# LM704A0_5V0_PINOUT.net
KiCad netlist of a schematic drawn in Altium Designer
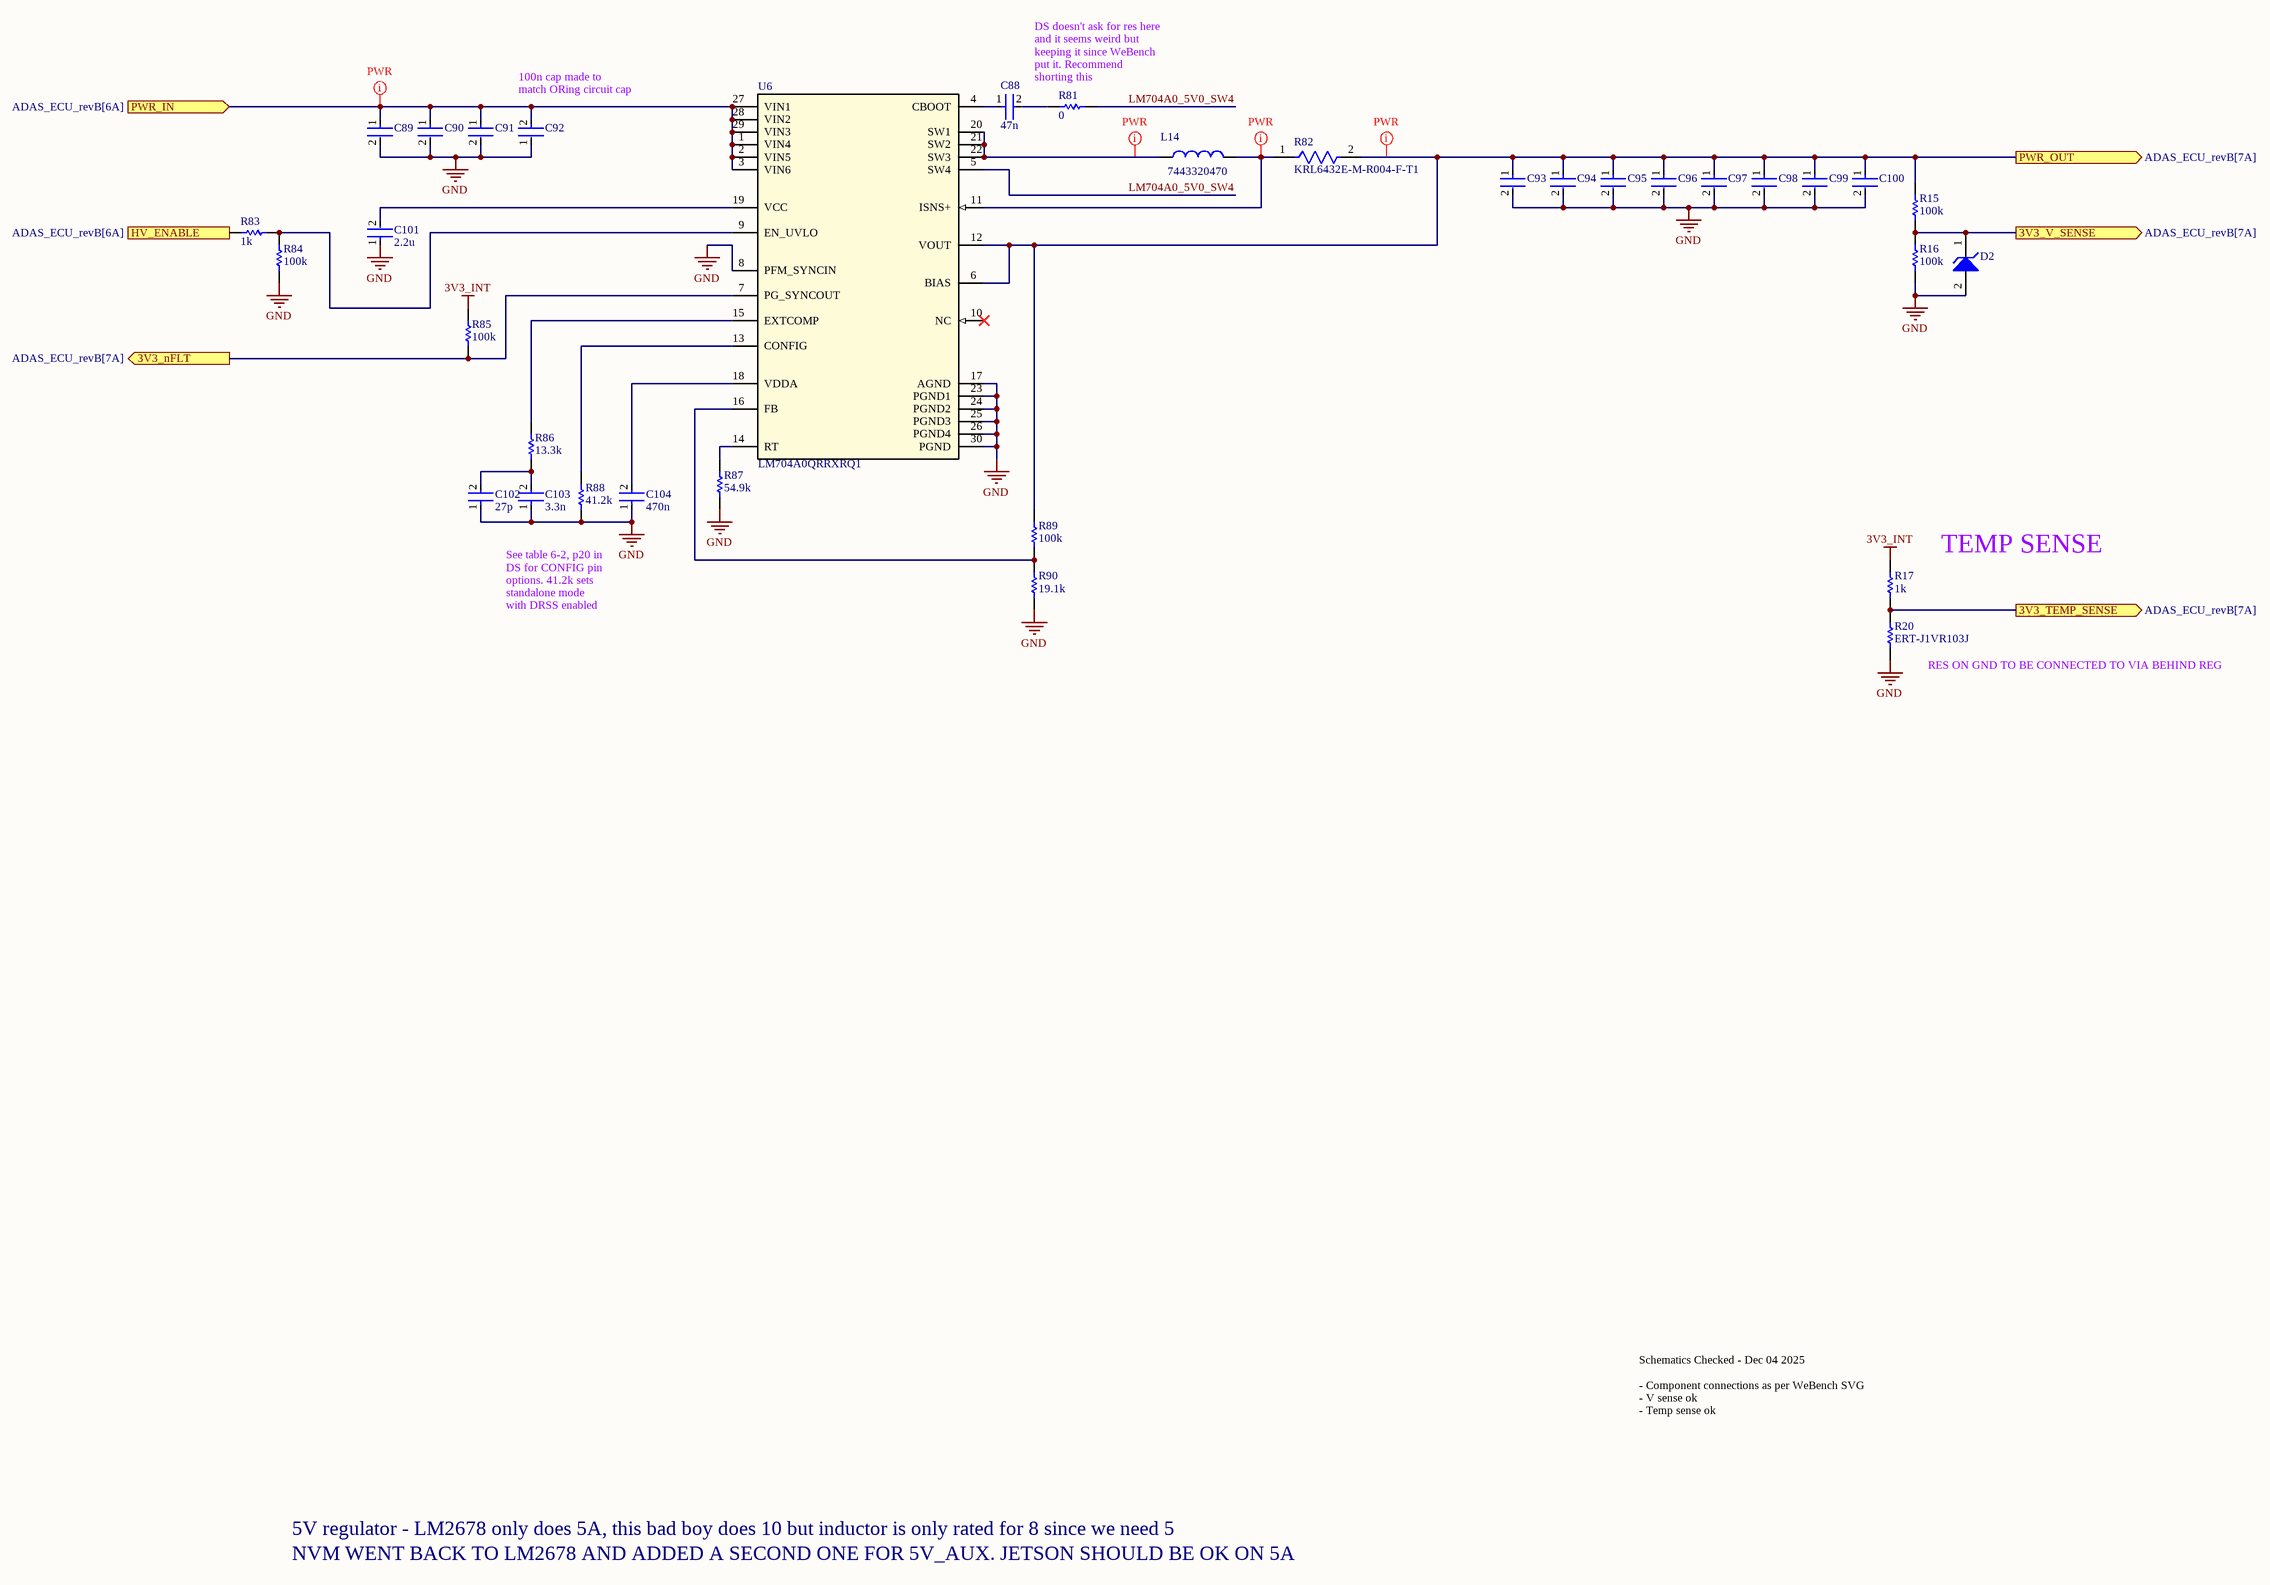
[diagram p0: LM704A0_5V0_PINOUT.SchDoc]

(export (version "E")
  (design (tool "Eeschema 10.0.6"))
  (components
    (comp (ref "C88")
      (value "47n")
      (footprint "FP-0402-L_1_0_0_05-W_0_5-IPC_A")
      (description "LARGE PADS, 0402 CAP, CHANGE COMMENT TO MATCH REAL P/N")
      (libsource (lib "Space Concordia") (part "b4654b650e69147ec39a6b967a45e02"))
    )
    (comp (ref "C89")
      (value "C3225X7R1H106M250AC")
      (footprint "FP-C3225-250-0_4-MFG")
      (description "Multilayer Ceramic Capacitors 10uF ±20% 50V X7R SMD 1210")
      (fields (field (name "TOLERANCE") "20%"))
      (libsource (lib "Altium Content Vault") (part "02cd4be3c70576c341d710602a673aa"))
    )
    (comp (ref "C90")
      (value "C3225X7R1H106M250AC")
      (footprint "FP-C3225-250-0_4-MFG")
      (description "Multilayer Ceramic Capacitors 10uF ±20% 50V X7R SMD 1210")
      (fields (field (name "TOLERANCE") "20%"))
      (libsource (lib "Altium Content Vault") (part "02cd4be3c70576c341d710602a673aa"))
    )
    (comp (ref "C91")
      (value "C3225X7R1H106M250AC")
      (footprint "FP-C3225-250-0_4-MFG")
      (description "Multilayer Ceramic Capacitors 10uF ±20% 50V X7R SMD 1210")
      (fields (field (name "TOLERANCE") "20%"))
      (libsource (lib "Altium Content Vault") (part "02cd4be3c70576c341d710602a673aa"))
    )
    (comp (ref "C92")
      (value "AC1210KKX7R0BB104")
      (footprint "FP-AC1210-0_85-MFG")
      (description "CAP CER 0.1UF 100V X7R 1210")
      (fields (field (name "MANUFACTURER") "Yageo") (field (name "TOLERANCE") "0.1"))
      (libsource (lib "Altium Content Vault") (part "236180d848d6139a670b325ea6854c9"))
    )
    (comp (ref "C93")
      (value "GRM32ER61C476KE15L")
      (footprint "FP-GRM32E-0_3-0_2-IPC_C")
      (description "CAP CER 47UF 16V X5R 1210")
      (fields (field (name "VOLTAGE") "16V") (field (name "TOLERANCE") "10%"))
      (libsource (lib "Altium Content Vault") (part "b4654b650e69147ec39a6b967a45e02"))
    )
    (comp (ref "C94")
      (value "GRM32ER61C476KE15L")
      (footprint "FP-GRM32E-0_3-0_2-IPC_C")
      (description "CAP CER 47UF 16V X5R 1210")
      (fields (field (name "VOLTAGE") "16V") (field (name "TOLERANCE") "10%"))
      (libsource (lib "Altium Content Vault") (part "b4654b650e69147ec39a6b967a45e02"))
    )
    (comp (ref "C95")
      (value "GRM32ER61C476KE15L")
      (footprint "FP-GRM32E-0_3-0_2-IPC_C")
      (description "CAP CER 47UF 16V X5R 1210")
      (fields (field (name "VOLTAGE") "16V") (field (name "TOLERANCE") "10%"))
      (libsource (lib "Altium Content Vault") (part "b4654b650e69147ec39a6b967a45e02"))
    )
    (comp (ref "C96")
      (value "GRM32ER61C476KE15L")
      (footprint "FP-GRM32E-0_3-0_2-IPC_C")
      (description "CAP CER 47UF 16V X5R 1210")
      (fields (field (name "VOLTAGE") "16V") (field (name "TOLERANCE") "10%"))
      (libsource (lib "Altium Content Vault") (part "b4654b650e69147ec39a6b967a45e02"))
    )
    (comp (ref "C97")
      (value "GRM32ER61C476KE15L")
      (footprint "FP-GRM32E-0_3-0_2-IPC_C")
      (description "CAP CER 47UF 16V X5R 1210")
      (fields (field (name "VOLTAGE") "16V") (field (name "TOLERANCE") "10%"))
      (libsource (lib "Altium Content Vault") (part "b4654b650e69147ec39a6b967a45e02"))
    )
    (comp (ref "C98")
      (value "GRM32ER61C476KE15L")
      (footprint "FP-GRM32E-0_3-0_2-IPC_C")
      (description "CAP CER 47UF 16V X5R 1210")
      (fields (field (name "VOLTAGE") "16V") (field (name "TOLERANCE") "10%"))
      (libsource (lib "Altium Content Vault") (part "b4654b650e69147ec39a6b967a45e02"))
    )
    (comp (ref "C99")
      (value "GRM32ER61C476KE15L")
      (footprint "FP-GRM32E-0_3-0_2-IPC_C")
      (description "CAP CER 47UF 16V X5R 1210")
      (fields (field (name "VOLTAGE") "16V") (field (name "TOLERANCE") "10%"))
      (libsource (lib "Altium Content Vault") (part "b4654b650e69147ec39a6b967a45e02"))
    )
    (comp (ref "C100")
      (value "GRM32ER61C476KE15L")
      (footprint "FP-GRM32E-0_3-0_2-IPC_C")
      (description "CAP CER 47UF 16V X5R 1210")
      (fields (field (name "VOLTAGE") "16V") (field (name "TOLERANCE") "10%"))
      (libsource (lib "Altium Content Vault") (part "b4654b650e69147ec39a6b967a45e02"))
    )
    (comp (ref "C101")
      (value "2.2u")
      (footprint "FP-0402-L_1_0_0_05-W_0_5-IPC_A")
      (description "LARGE PADS, 0402 CAP, CHANGE COMMENT TO MATCH REAL P/N")
      (libsource (lib "Space Concordia") (part "b4654b650e69147ec39a6b967a45e02"))
    )
    (comp (ref "C102")
      (value "27p")
      (footprint "FP-0402-L_1_0_0_05-W_0_5-IPC_A")
      (description "LARGE PADS, 0402 CAP, CHANGE COMMENT TO MATCH REAL P/N")
      (libsource (lib "Space Concordia") (part "b4654b650e69147ec39a6b967a45e02"))
    )
    (comp (ref "C103")
      (value "3.3n")
      (footprint "FP-0402-L_1_0_0_05-W_0_5-IPC_A")
      (description "LARGE PADS, 0402 CAP, CHANGE COMMENT TO MATCH REAL P/N")
      (libsource (lib "Space Concordia") (part "b4654b650e69147ec39a6b967a45e02"))
    )
    (comp (ref "C104")
      (value "470n")
      (footprint "FP-0402-L_1_0_0_05-W_0_5-IPC_A")
      (description "LARGE PADS, 0402 CAP, CHANGE COMMENT TO MATCH REAL P/N")
      (libsource (lib "Space Concordia") (part "b4654b650e69147ec39a6b967a45e02"))
    )
    (comp (ref "D2")
      (value "MM5Z3V3T1G")
      (footprint "ONSC-SOD-523-2-502-01_V")
      (description "Zener Voltage Regulator, 500 mW, 2-Pin SOD-523, Pb-Free, Tape and Reel")
      (fields (field (name "MANUFACTURER") "On Semiconductor"))
      (libsource (lib "Altium Content Vault") (part "ONSC-K1A2-2"))
    )
    (comp (ref "L14")
      (value "7443320470")
      (footprint "WE-HCC_1210")
      (description "We-hcc Series, Shielded Wire-wound SMD Inductor With Ferrite Core, 4.7 Uh")
      (libsource (lib "Altium Content Vault") (part "Inductor - 1"))
    )
    (comp (ref "R15")
      (value "100k")
      (footprint "R0603B")
      (description "Resistor")
      (libsource (lib "Space Concordia") (part "Resistor"))
    )
    (comp (ref "R16")
      (value "100k")
      (footprint "R0603B")
      (description "Resistor")
      (libsource (lib "Space Concordia") (part "Resistor"))
    )
    (comp (ref "R17")
      (value "1k")
      (footprint "R0603B")
      (description "Resistor")
      (libsource (lib "Space Concordia") (part "Resistor"))
    )
    (comp (ref "R20")
      (value "ERT-J1VR103J")
      (footprint "RESC1608X90X30ML15T20")
      (fields (field (name "MANUFACTURER") "Panasonic"))
      (libsource (lib "Altium Content Vault") (part "RES"))
    )
    (comp (ref "R81")
      (value "0")
      (footprint "R0603B")
      (description "Resistor")
      (libsource (lib "Space Concordia") (part "Resistor"))
    )
    (comp (ref "R82")
      (value "KRL6432E-M-R004-F-T1")
      (footprint "FP-KRL6432E-MFG")
      (description "KRL6432E-M-R004-F-T1 Metal Foil Low Resistance Chip Resistor (long-side terminal), 2512, RoHS")
      (fields (field (name "TOLERANCE") "1%"))
      (libsource (lib "Altium Content Vault") (part "1029c3af85768c4190bb7ad29bc67b5"))
    )
    (comp (ref "R83")
      (value "1k")
      (footprint "R0603B")
      (description "Resistor")
      (libsource (lib "Space Concordia") (part "Resistor"))
    )
    (comp (ref "R84")
      (value "100k")
      (footprint "R0603B")
      (description "Resistor")
      (libsource (lib "Space Concordia") (part "Resistor"))
    )
    (comp (ref "R85")
      (value "100k")
      (footprint "R0603B")
      (description "Resistor")
      (libsource (lib "Space Concordia") (part "Resistor"))
    )
    (comp (ref "R86")
      (value "13.3k")
      (footprint "R0603B")
      (description "Resistor")
      (libsource (lib "Space Concordia") (part "Resistor"))
    )
    (comp (ref "R87")
      (value "54.9k")
      (footprint "R0603B")
      (description "Resistor")
      (libsource (lib "Space Concordia") (part "Resistor"))
    )
    (comp (ref "R88")
      (value "41.2k")
      (footprint "R0603B")
      (description "Resistor")
      (libsource (lib "Space Concordia") (part "Resistor"))
    )
    (comp (ref "R89")
      (value "100k")
      (footprint "R0603B")
      (description "Resistor")
      (libsource (lib "Space Concordia") (part "Resistor"))
    )
    (comp (ref "R90")
      (value "19.1k")
      (footprint "R0603B")
      (description "Resistor")
      (libsource (lib "Space Concordia") (part "Resistor"))
    )
    (comp (ref "U6")
      (value "LM704A0QRRXRQ1")
      (footprint "LM704A0QRRXRQ1-Footprint-1")
      (libsource (lib "Space Concordia") (part "LM704A0QRRXRQ1"))
    )
  )
  (nets
    (net (code "1") (name "/3V3_TEMP_SENSE") (class "Default")
      (node (ref "R17") (pin "2") (pinfunction "2_2") (pintype "passive"))
      (node (ref "R20") (pin "2") (pinfunction "2_2") (pintype "passive"))
    )
    (net (code "2") (name "/3V3_V_SENSE") (class "Default")
      (node (ref "D2") (pin "1") (pinfunction "K_1") (pintype "passive"))
      (node (ref "R15") (pin "2") (pinfunction "2_2") (pintype "passive"))
      (node (ref "R16") (pin "1") (pinfunction "1_1") (pintype "passive"))
    )
    (net (code "3") (name "/3V3_nFLT") (class "Default")
      (node (ref "R85") (pin "1") (pinfunction "1_1") (pintype "passive"))
      (node (ref "U6") (pin "7") (pinfunction "PG_SYNCOUT_7") (pintype "passive"))
    )
    (net (code "4") (name "/HV_ENABLE") (class "Default")
      (node (ref "R83") (pin "2") (pinfunction "2_2") (pintype "passive"))
    )
    (net (code "5") (name "/LM704A0_5V0_SW4") (class "Default")
      (node (ref "R81") (pin "2") (pinfunction "2_2") (pintype "passive"))
      (node (ref "U6") (pin "5") (pinfunction "SW4_5") (pintype "power_in"))
    )
    (net (code "6") (name "/PWR_IN") (class "Default")
      (node (ref "C89") (pin "1") (pinfunction "1_1") (pintype "passive"))
      (node (ref "C90") (pin "1") (pinfunction "1_1") (pintype "passive"))
      (node (ref "C91") (pin "1") (pinfunction "1_1") (pintype "passive"))
      (node (ref "C92") (pin "2") (pinfunction "2_2") (pintype "passive"))
      (node (ref "U6") (pin "1") (pinfunction "VIN4_1") (pintype "passive"))
      (node (ref "U6") (pin "2") (pinfunction "VIN5_2") (pintype "passive"))
      (node (ref "U6") (pin "27") (pinfunction "VIN1_27") (pintype "power_in"))
      (node (ref "U6") (pin "28") (pinfunction "VIN2_28") (pintype "power_in"))
      (node (ref "U6") (pin "29") (pinfunction "VIN3_29") (pintype "power_in"))
      (node (ref "U6") (pin "3") (pinfunction "VIN6_3") (pintype "power_in"))
    )
    (net (code "7") (name "/PWR_OUT") (class "Default")
      (node (ref "C100") (pin "1") (pinfunction "1_1") (pintype "passive"))
      (node (ref "C93") (pin "1") (pinfunction "1_1") (pintype "passive"))
      (node (ref "C94") (pin "1") (pinfunction "1_1") (pintype "passive"))
      (node (ref "C95") (pin "1") (pinfunction "1_1") (pintype "passive"))
      (node (ref "C96") (pin "1") (pinfunction "1_1") (pintype "passive"))
      (node (ref "C97") (pin "1") (pinfunction "1_1") (pintype "passive"))
      (node (ref "C98") (pin "1") (pinfunction "1_1") (pintype "passive"))
      (node (ref "C99") (pin "1") (pinfunction "1_1") (pintype "passive"))
      (node (ref "R15") (pin "1") (pinfunction "1_1") (pintype "passive"))
      (node (ref "R82") (pin "2") (pinfunction "2_2") (pintype "passive"))
      (node (ref "R89") (pin "1") (pinfunction "1_1") (pintype "passive"))
      (node (ref "U6") (pin "12") (pinfunction "VOUT_12") (pintype "passive"))
      (node (ref "U6") (pin "6") (pinfunction "BIAS_6") (pintype "passive"))
    )
    (net (code "8") (name "3V3_INT") (class "Default")
      (node (ref "R17") (pin "1") (pinfunction "1_1") (pintype "passive"))
      (node (ref "R85") (pin "2") (pinfunction "2_2") (pintype "passive"))
    )
    (net (code "9") (name "GND") (class "Default")
      (node (ref "C100") (pin "2") (pinfunction "2_2") (pintype "passive"))
      (node (ref "C101") (pin "1") (pinfunction "1_1") (pintype "passive"))
      (node (ref "C102") (pin "1") (pinfunction "1_1") (pintype "passive"))
      (node (ref "C103") (pin "1") (pinfunction "1_1") (pintype "passive"))
      (node (ref "C104") (pin "1") (pinfunction "1_1") (pintype "passive"))
      (node (ref "C89") (pin "2") (pinfunction "2_2") (pintype "passive"))
      (node (ref "C90") (pin "2") (pinfunction "2_2") (pintype "passive"))
      (node (ref "C91") (pin "2") (pinfunction "2_2") (pintype "passive"))
      (node (ref "C92") (pin "1") (pinfunction "1_1") (pintype "passive"))
      (node (ref "C93") (pin "2") (pinfunction "2_2") (pintype "passive"))
      (node (ref "C94") (pin "2") (pinfunction "2_2") (pintype "passive"))
      (node (ref "C95") (pin "2") (pinfunction "2_2") (pintype "passive"))
      (node (ref "C96") (pin "2") (pinfunction "2_2") (pintype "passive"))
      (node (ref "C97") (pin "2") (pinfunction "2_2") (pintype "passive"))
      (node (ref "C98") (pin "2") (pinfunction "2_2") (pintype "passive"))
      (node (ref "C99") (pin "2") (pinfunction "2_2") (pintype "passive"))
      (node (ref "D2") (pin "2") (pinfunction "A_2") (pintype "passive"))
      (node (ref "R16") (pin "2") (pinfunction "2_2") (pintype "passive"))
      (node (ref "R20") (pin "1") (pinfunction "1_1") (pintype "passive"))
      (node (ref "R84") (pin "1") (pinfunction "1_1") (pintype "passive"))
      (node (ref "R87") (pin "2") (pinfunction "2_2") (pintype "passive"))
      (node (ref "R88") (pin "2") (pinfunction "2_2") (pintype "passive"))
      (node (ref "R90") (pin "2") (pinfunction "2_2") (pintype "passive"))
      (node (ref "U6") (pin "17") (pinfunction "AGND_17") (pintype "passive"))
      (node (ref "U6") (pin "23") (pinfunction "PGND1_23") (pintype "passive"))
      (node (ref "U6") (pin "24") (pinfunction "PGND2_24") (pintype "passive"))
      (node (ref "U6") (pin "25") (pinfunction "PGND3_25") (pintype "power_in"))
      (node (ref "U6") (pin "26") (pinfunction "PGND4_26") (pintype "power_in"))
      (node (ref "U6") (pin "30") (pinfunction "PGND_30") (pintype "power_in"))
      (node (ref "U6") (pin "8") (pinfunction "PFM_SYNCIN_8") (pintype "power_in"))
    )
    (net (code "10") (name "Net-(C88-Pad2)") (class "Default")
      (node (ref "C88") (pin "2") (pinfunction "2_2") (pintype "passive"))
      (node (ref "R81") (pin "1") (pinfunction "1_1") (pintype "passive"))
    )
    (net (code "11") (name "Net-(C102-Pad2)") (class "Default")
      (node (ref "C102") (pin "2") (pinfunction "2_2") (pintype "passive"))
      (node (ref "C103") (pin "2") (pinfunction "2_2") (pintype "passive"))
      (node (ref "R86") (pin "1") (pinfunction "1_1") (pintype "passive"))
    )
    (net (code "12") (name "Net-(U6-CBOOT)") (class "Default")
      (node (ref "C88") (pin "1") (pinfunction "1_1") (pintype "passive"))
      (node (ref "U6") (pin "4") (pinfunction "CBOOT_4") (pintype "power_in"))
    )
    (net (code "13") (name "Net-(U6-CONFIG)") (class "Default")
      (node (ref "R88") (pin "1") (pinfunction "1_1") (pintype "passive"))
      (node (ref "U6") (pin "13") (pinfunction "CONFIG_13") (pintype "passive"))
    )
    (net (code "14") (name "Net-(U6-EN_UVLO)") (class "Default")
      (node (ref "R83") (pin "1") (pinfunction "1_1") (pintype "passive"))
      (node (ref "R84") (pin "2") (pinfunction "2_2") (pintype "passive"))
      (node (ref "U6") (pin "9") (pinfunction "EN_UVLO_9") (pintype "open_collector"))
    )
    (net (code "15") (name "Net-(U6-EXTCOMP)") (class "Default")
      (node (ref "R86") (pin "2") (pinfunction "2_2") (pintype "passive"))
      (node (ref "U6") (pin "15") (pinfunction "EXTCOMP_15") (pintype "passive"))
    )
    (net (code "16") (name "Net-(U6-FB)") (class "Default")
      (node (ref "R89") (pin "2") (pinfunction "2_2") (pintype "passive"))
      (node (ref "R90") (pin "1") (pinfunction "1_1") (pintype "passive"))
      (node (ref "U6") (pin "16") (pinfunction "FB_16") (pintype "passive"))
    )
    (net (code "17") (name "Net-(U6-ISNS+)") (class "Default")
      (node (ref "L14") (pin "2") (pinfunction "2_2") (pintype "passive"))
      (node (ref "R82") (pin "1") (pinfunction "1_1") (pintype "passive"))
      (node (ref "U6") (pin "11") (pinfunction "ISNS+_11") (pintype "input"))
    )
    (net (code "18") (name "Net-(U6-RT)") (class "Default")
      (node (ref "R87") (pin "1") (pinfunction "1_1") (pintype "passive"))
      (node (ref "U6") (pin "14") (pinfunction "RT_14") (pintype "passive"))
    )
    (net (code "19") (name "Net-(U6-SW1)") (class "Default")
      (node (ref "L14") (pin "1") (pinfunction "1_1") (pintype "passive"))
      (node (ref "U6") (pin "20") (pinfunction "SW1_20") (pintype "power_in"))
      (node (ref "U6") (pin "21") (pinfunction "SW2_21") (pintype "power_in"))
      (node (ref "U6") (pin "22") (pinfunction "SW3_22") (pintype "passive"))
    )
    (net (code "20") (name "Net-(U6-VCC)") (class "Default")
      (node (ref "C101") (pin "2") (pinfunction "2_2") (pintype "passive"))
      (node (ref "U6") (pin "19") (pinfunction "VCC_19") (pintype "power_in"))
    )
    (net (code "21") (name "Net-(U6-VDDA)") (class "Default")
      (node (ref "C104") (pin "2") (pinfunction "2_2") (pintype "passive"))
      (node (ref "U6") (pin "18") (pinfunction "VDDA_18") (pintype "passive"))
    )
    (net (code "22") (name "unconnected-(U6-NC-Pad10)") (class "Default")
      (node (ref "U6") (pin "10") (pinfunction "NC_10") (pintype "input+no_connect"))
    )
  )
)
